# 1-Schematic_INFRARED_WAVER_V1.net
KiCad netlist of a schematic drawn in EasyEDA
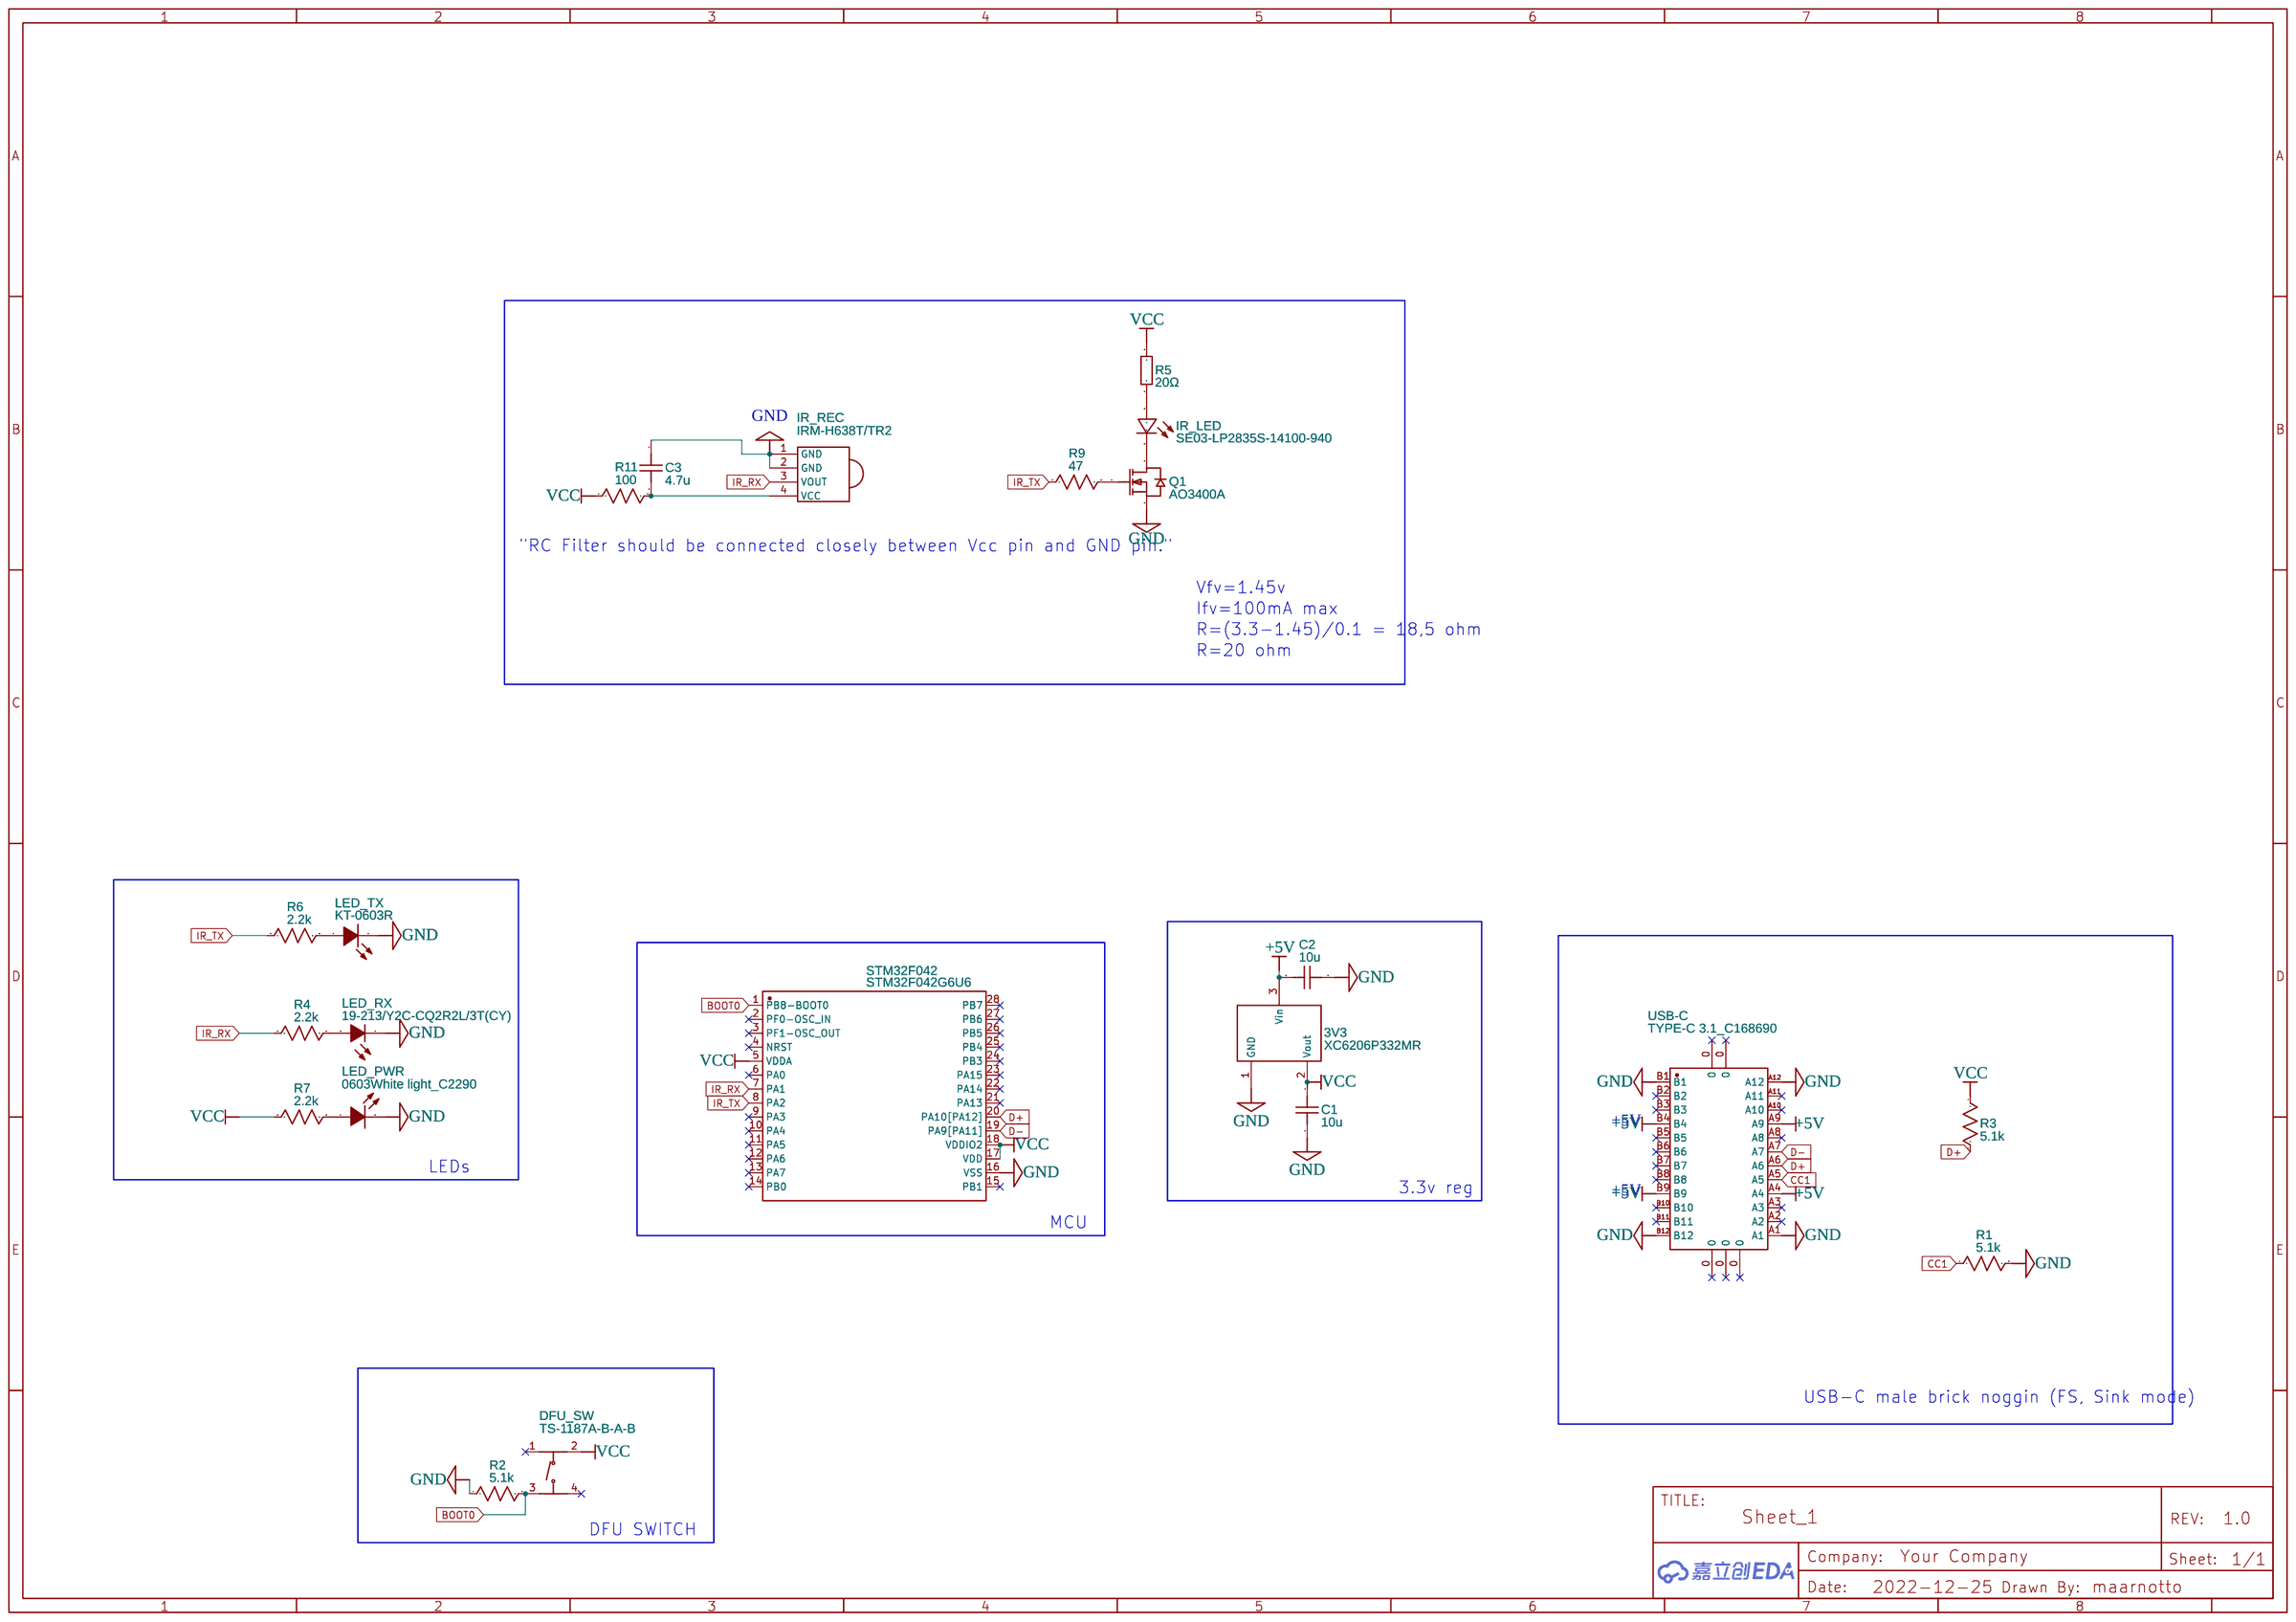
[diagram p0: schematic sheet]

(export (version "E")
  (design (tool "Eeschema 10.0.6"))
  (components
    (comp (ref "3V3")
      (value "XC6206P332MR")
      (fields (field (name "Manufacturer") "TOREX(特瑞仕)"))
      (libsource (lib "") (part "XC6206P332MR"))
    )
    (comp (ref "C1") (value "10u") (libsource (lib "") (part "C_0603_US_1")))
    (comp (ref "C2") (value "10u") (libsource (lib "") (part "C_0603_US")))
    (comp (ref "C3") (value "4.7u") (libsource (lib "") (part "C_0603_US_1")))
    (comp (ref "DFU_SW")
      (value "TS-1187A-B-A-B")
      (fields (field (name "Manufacturer") "XKB Connectivity(中国星坤)"))
      (libsource (lib "") (part "TS-1187A-B-A-B"))
    )
    (comp (ref "IR_LED")
      (value "SE03-LP2835S-14100-940")
      (fields (field (name "Manufacturer") "XSSY(旭晟)"))
      (libsource (lib "") (part "SE03-LP2835S-14100-940"))
    )
    (comp (ref "IR_REC")
      (value "IRM-H638T/TR2")
      (fields (field (name "Manufacturer") "EVERLIGHT(亿光)"))
      (libsource (lib "") (part "IRM-H638T/TR2"))
    )
    (comp (ref "LED_PWR")
      (value "0603White light_C2290")
      (fields (field (name "Manufacturer Part") "KT-0603白灯"))
      (libsource (lib "") (part "0603White light_C2290"))
    )
    (comp (ref "LED_RX")
      (value "19-213/Y2C-CQ2R2L/3T(CY)")
      (fields (field (name "Manufacturer") "EVERLIGHT(亿光)"))
      (libsource (lib "") (part "19-213/Y2C-CQ2R2L/3T(CY)"))
    )
    (comp (ref "LED_TX")
      (value "KT-0603R")
      (fields (field (name "Manufacturer") "KENTO"))
      (libsource (lib "") (part "KT-0603R"))
    )
    (comp (ref "Q1")
      (value "AO3400A")
      (fields (field (name "Manufacturer") "AOS"))
      (libsource (lib "") (part "AO3400A"))
    )
    (comp (ref "R1") (value "5.1k") (libsource (lib "") (part "R_0603_US_1")))
    (comp (ref "R2") (value "5.1k") (libsource (lib "") (part "R_0603_US_1")))
    (comp (ref "R3") (value "5.1k") (libsource (lib "") (part "R_0603_US")))
    (comp (ref "R4") (value "2.2k") (libsource (lib "") (part "R_0603_US_1")))
    (comp (ref "R5")
      (value "20Ω")
      (fields
        (field (name "Manufacturer Part") "1206W4F200JT5E")
        (field (name "Manufacturer") "UNI-ROYAL(厚声)")
      )
      (libsource (lib "") (part "1206W4F200JT5E"))
    )
    (comp (ref "R6") (value "2.2k") (libsource (lib "") (part "R_0603_US_1")))
    (comp (ref "R7") (value "2.2k") (libsource (lib "") (part "R_0603_US_1")))
    (comp (ref "R9") (value "47") (libsource (lib "") (part "R_0603_US_1")))
    (comp (ref "R11") (value "100") (libsource (lib "") (part "R_0603_US_1")))
    (comp (ref "STM32F042")
      (value "STM32F042G6U6")
      (fields (field (name "Manufacturer") "ST(意法半导体)"))
      (libsource (lib "") (part "STM32F042G6U6"))
    )
    (comp (ref "USB-C")
      (value "TYPE-C 3.1_C168690")
      (fields (field (name "Manufacturer Part") "918-118A2021Y40000") (field (name "Manufacturer") "精拓金"))
      (libsource (lib "") (part "TYPE-C 3.1_C168690"))
    )
  )
  (nets
    (net (code "1") (name "+5V") (class "Default")
      (node (ref "3V3") (pin "3") (pinfunction "Vin_3") (pintype "unspecified"))
      (node (ref "C2") (pin "2") (pinfunction "2_2") (pintype "unspecified"))
      (node (ref "USB-C") (pin "A4") (pinfunction "A4_A4") (pintype "unspecified"))
      (node (ref "USB-C") (pin "A9") (pinfunction "A9_A9") (pintype "unspecified"))
      (node (ref "USB-C") (pin "B4") (pinfunction "B4_B4") (pintype "unspecified"))
      (node (ref "USB-C") (pin "B9") (pinfunction "B9_B9") (pintype "unspecified"))
    )
    (net (code "2") (name "BOOT0") (class "Default")
      (node (ref "DFU_SW") (pin "3") (pinfunction "C_3") (pintype "unspecified"))
      (node (ref "R2") (pin "2") (pinfunction "2_2") (pintype "unspecified"))
      (node (ref "STM32F042") (pin "1") (pinfunction "PB8-BOOT0_1") (pintype "unspecified"))
    )
    (net (code "3") (name "CC1") (class "Default")
      (node (ref "R1") (pin "1") (pinfunction "1_1") (pintype "unspecified"))
      (node (ref "USB-C") (pin "A5") (pinfunction "A5_A5") (pintype "unspecified"))
    )
    (net (code "4") (name "D+") (class "Default")
      (node (ref "R3") (pin "2") (pinfunction "2_2") (pintype "unspecified"))
      (node (ref "STM32F042") (pin "20") (pinfunction "PA10[PA12]_20") (pintype "unspecified"))
      (node (ref "USB-C") (pin "A6") (pinfunction "A6_A6") (pintype "unspecified"))
    )
    (net (code "5") (name "D-") (class "Default")
      (node (ref "STM32F042") (pin "19") (pinfunction "PA9[PA11]_19") (pintype "unspecified"))
      (node (ref "USB-C") (pin "A7") (pinfunction "A7_A7") (pintype "unspecified"))
    )
    (net (code "6") (name "GND") (class "Default")
      (node (ref "3V3") (pin "1") (pinfunction "GND_1") (pintype "unspecified"))
      (node (ref "C1") (pin "2") (pinfunction "2_2") (pintype "unspecified"))
      (node (ref "C2") (pin "1") (pinfunction "1_1") (pintype "unspecified"))
      (node (ref "C3") (pin "1") (pinfunction "1_1") (pintype "unspecified"))
      (node (ref "IR_REC") (pin "1") (pinfunction "GND_1") (pintype "input"))
      (node (ref "IR_REC") (pin "2") (pinfunction "GND_2") (pintype "input"))
      (node (ref "LED_PWR") (pin "2") (pinfunction "K_2") (pintype "unspecified"))
      (node (ref "LED_RX") (pin "1") (pinfunction "C_1") (pintype "input"))
      (node (ref "LED_TX") (pin "1") (pinfunction "K_1") (pintype "unspecified"))
      (node (ref "Q1") (pin "2") (pinfunction "S_2") (pintype "unspecified"))
      (node (ref "R1") (pin "2") (pinfunction "2_2") (pintype "unspecified"))
      (node (ref "R2") (pin "1") (pinfunction "1_1") (pintype "unspecified"))
      (node (ref "STM32F042") (pin "16") (pinfunction "VSS_16") (pintype "unspecified"))
      (node (ref "USB-C") (pin "A1") (pinfunction "A1_A1") (pintype "unspecified"))
      (node (ref "USB-C") (pin "A12") (pinfunction "A12_A12") (pintype "unspecified"))
      (node (ref "USB-C") (pin "B1") (pinfunction "B1_B1") (pintype "unspecified"))
      (node (ref "USB-C") (pin "B12") (pinfunction "B12_B12") (pintype "unspecified"))
    )
    (net (code "7") (name "IR_RX") (class "Default")
      (node (ref "IR_REC") (pin "3") (pinfunction "VOUT_3") (pintype "input"))
      (node (ref "R4") (pin "1") (pinfunction "1_1") (pintype "unspecified"))
      (node (ref "STM32F042") (pin "7") (pinfunction "PA1_7") (pintype "unspecified"))
    )
    (net (code "8") (name "IR_TX") (class "Default")
      (node (ref "R6") (pin "1") (pinfunction "1_1") (pintype "unspecified"))
      (node (ref "R9") (pin "1") (pinfunction "1_1") (pintype "unspecified"))
      (node (ref "STM32F042") (pin "8") (pinfunction "PA2_8") (pintype "unspecified"))
    )
    (net (code "9") (name "Net-(IR_LED-A)") (class "Default")
      (node (ref "IR_LED") (pin "1") (pinfunction "A_1") (pintype "unspecified"))
      (node (ref "R5") (pin "2") (pinfunction "2_2") (pintype "input"))
    )
    (net (code "10") (name "Net-(IR_LED-C)") (class "Default")
      (node (ref "IR_LED") (pin "2") (pinfunction "C_2") (pintype "unspecified"))
      (node (ref "Q1") (pin "3") (pinfunction "D_3") (pintype "unspecified"))
    )
    (net (code "11") (name "Net-(IR_REC-VCC)") (class "Default")
      (node (ref "C3") (pin "2") (pinfunction "2_2") (pintype "unspecified"))
      (node (ref "IR_REC") (pin "4") (pinfunction "VCC_4") (pintype "input"))
      (node (ref "R11") (pin "2") (pinfunction "2_2") (pintype "unspecified"))
    )
    (net (code "12") (name "Net-(LED_PWR-A)") (class "Default")
      (node (ref "LED_PWR") (pin "1") (pinfunction "A_1") (pintype "unspecified"))
      (node (ref "R7") (pin "2") (pinfunction "2_2") (pintype "unspecified"))
    )
    (net (code "13") (name "Net-(LED_RX-A)") (class "Default")
      (node (ref "LED_RX") (pin "2") (pinfunction "A_2") (pintype "input"))
      (node (ref "R4") (pin "2") (pinfunction "2_2") (pintype "unspecified"))
    )
    (net (code "14") (name "Net-(LED_TX-A)") (class "Default")
      (node (ref "LED_TX") (pin "2") (pinfunction "A_2") (pintype "unspecified"))
      (node (ref "R6") (pin "2") (pinfunction "2_2") (pintype "unspecified"))
    )
    (net (code "15") (name "Net-(Q1-G)") (class "Default")
      (node (ref "Q1") (pin "1") (pinfunction "G_1") (pintype "unspecified"))
      (node (ref "R9") (pin "2") (pinfunction "2_2") (pintype "unspecified"))
    )
    (net (code "16") (name "VCC") (class "Default")
      (node (ref "3V3") (pin "2") (pinfunction "Vout_2") (pintype "unspecified"))
      (node (ref "C1") (pin "1") (pinfunction "1_1") (pintype "unspecified"))
      (node (ref "DFU_SW") (pin "2") (pinfunction "B_2") (pintype "unspecified"))
      (node (ref "R11") (pin "1") (pinfunction "1_1") (pintype "unspecified"))
      (node (ref "R3") (pin "1") (pinfunction "1_1") (pintype "unspecified"))
      (node (ref "R5") (pin "1") (pinfunction "1_1") (pintype "input"))
      (node (ref "R7") (pin "1") (pinfunction "1_1") (pintype "unspecified"))
      (node (ref "STM32F042") (pin "17") (pinfunction "VDD_17") (pintype "unspecified"))
      (node (ref "STM32F042") (pin "18") (pinfunction "VDDIO2_18") (pintype "unspecified"))
      (node (ref "STM32F042") (pin "5") (pinfunction "VDDA_5") (pintype "unspecified"))
    )
    (net (code "17") (name "unconnected-(DFU_SW-A-Pad1)") (class "Default")
      (node (ref "DFU_SW") (pin "1") (pinfunction "A_1") (pintype "unspecified+no_connect"))
    )
    (net (code "18") (name "unconnected-(DFU_SW-D-Pad4)") (class "Default")
      (node (ref "DFU_SW") (pin "4") (pinfunction "D_4") (pintype "unspecified+no_connect"))
    )
    (net (code "19") (name "unconnected-(STM32F042-NRST-Pad4)") (class "Default")
      (node (ref "STM32F042") (pin "4") (pinfunction "NRST_4") (pintype "unspecified+no_connect"))
    )
    (net (code "20") (name "unconnected-(STM32F042-PA0-Pad6)") (class "Default")
      (node (ref "STM32F042") (pin "6") (pinfunction "PA0_6") (pintype "unspecified+no_connect"))
    )
    (net (code "21") (name "unconnected-(STM32F042-PA3-Pad9)") (class "Default")
      (node (ref "STM32F042") (pin "9") (pinfunction "PA3_9") (pintype "unspecified+no_connect"))
    )
    (net (code "22") (name "unconnected-(STM32F042-PA4-Pad10)") (class "Default")
      (node (ref "STM32F042") (pin "10") (pinfunction "PA4_10") (pintype "unspecified+no_connect"))
    )
    (net (code "23") (name "unconnected-(STM32F042-PA5-Pad11)") (class "Default")
      (node (ref "STM32F042") (pin "11") (pinfunction "PA5_11") (pintype "unspecified+no_connect"))
    )
    (net (code "24") (name "unconnected-(STM32F042-PA6-Pad12)") (class "Default")
      (node (ref "STM32F042") (pin "12") (pinfunction "PA6_12") (pintype "unspecified+no_connect"))
    )
    (net (code "25") (name "unconnected-(STM32F042-PA7-Pad13)") (class "Default")
      (node (ref "STM32F042") (pin "13") (pinfunction "PA7_13") (pintype "unspecified+no_connect"))
    )
    (net (code "26") (name "unconnected-(STM32F042-PA13-Pad21)") (class "Default")
      (node (ref "STM32F042") (pin "21") (pinfunction "PA13_21") (pintype "unspecified+no_connect"))
    )
    (net (code "27") (name "unconnected-(STM32F042-PA14-Pad22)") (class "Default")
      (node (ref "STM32F042") (pin "22") (pinfunction "PA14_22") (pintype "unspecified+no_connect"))
    )
    (net (code "28") (name "unconnected-(STM32F042-PA15-Pad23)") (class "Default")
      (node (ref "STM32F042") (pin "23") (pinfunction "PA15_23") (pintype "unspecified+no_connect"))
    )
    (net (code "29") (name "unconnected-(STM32F042-PB0-Pad14)") (class "Default")
      (node (ref "STM32F042") (pin "14") (pinfunction "PB0_14") (pintype "unspecified+no_connect"))
    )
    (net (code "30") (name "unconnected-(STM32F042-PB1-Pad15)") (class "Default")
      (node (ref "STM32F042") (pin "15") (pinfunction "PB1_15") (pintype "unspecified+no_connect"))
    )
    (net (code "31") (name "unconnected-(STM32F042-PB3-Pad24)") (class "Default")
      (node (ref "STM32F042") (pin "24") (pinfunction "PB3_24") (pintype "unspecified+no_connect"))
    )
    (net (code "32") (name "unconnected-(STM32F042-PB4-Pad25)") (class "Default")
      (node (ref "STM32F042") (pin "25") (pinfunction "PB4_25") (pintype "unspecified+no_connect"))
    )
    (net (code "33") (name "unconnected-(STM32F042-PB5-Pad26)") (class "Default")
      (node (ref "STM32F042") (pin "26") (pinfunction "PB5_26") (pintype "unspecified+no_connect"))
    )
    (net (code "34") (name "unconnected-(STM32F042-PB6-Pad27)") (class "Default")
      (node (ref "STM32F042") (pin "27") (pinfunction "PB6_27") (pintype "unspecified+no_connect"))
    )
    (net (code "35") (name "unconnected-(STM32F042-PB7-Pad28)") (class "Default")
      (node (ref "STM32F042") (pin "28") (pinfunction "PB7_28") (pintype "unspecified+no_connect"))
    )
    (net (code "36") (name "unconnected-(STM32F042-PF0-OSC_IN-Pad2)") (class "Default")
      (node (ref "STM32F042") (pin "2") (pinfunction "PF0-OSC_IN_2") (pintype "unspecified+no_connect"))
    )
    (net (code "37") (name "unconnected-(STM32F042-PF1-OSC_OUT-Pad3)") (class "Default")
      (node (ref "STM32F042") (pin "3") (pinfunction "PF1-OSC_OUT_3") (pintype "unspecified+no_connect"))
    )
    (net (code "38") (name "unconnected-(USB-C-Pad0)") (class "Default")
      (node (ref "USB-C") (pin "0") (pinfunction "0_0") (pintype "unspecified+no_connect"))
    )
    (net (code "39") (name "unconnected-(USB-C-Pad0)_1") (class "Default")
      (node (ref "USB-C") (pin "0") (pinfunction "0_0") (pintype "unspecified+no_connect"))
    )
    (net (code "40") (name "unconnected-(USB-C-Pad0)_2") (class "Default")
      (node (ref "USB-C") (pin "0") (pinfunction "0_0") (pintype "unspecified+no_connect"))
    )
    (net (code "41") (name "unconnected-(USB-C-Pad0)_3") (class "Default")
      (node (ref "USB-C") (pin "0") (pinfunction "0_0") (pintype "unspecified+no_connect"))
    )
    (net (code "42") (name "unconnected-(USB-C-Pad0)_4") (class "Default")
      (node (ref "USB-C") (pin "0") (pinfunction "0_0") (pintype "unspecified+no_connect"))
    )
    (net (code "43") (name "unconnected-(USB-C-PadA2)") (class "Default")
      (node (ref "USB-C") (pin "A2") (pinfunction "A2_A2") (pintype "unspecified+no_connect"))
    )
    (net (code "44") (name "unconnected-(USB-C-PadA3)") (class "Default")
      (node (ref "USB-C") (pin "A3") (pinfunction "A3_A3") (pintype "unspecified+no_connect"))
    )
    (net (code "45") (name "unconnected-(USB-C-PadA8)") (class "Default")
      (node (ref "USB-C") (pin "A8") (pinfunction "A8_A8") (pintype "unspecified+no_connect"))
    )
    (net (code "46") (name "unconnected-(USB-C-PadA10)") (class "Default")
      (node (ref "USB-C") (pin "A10") (pinfunction "A10_A10") (pintype "unspecified+no_connect"))
    )
    (net (code "47") (name "unconnected-(USB-C-PadA11)") (class "Default")
      (node (ref "USB-C") (pin "A11") (pinfunction "A11_A11") (pintype "unspecified+no_connect"))
    )
    (net (code "48") (name "unconnected-(USB-C-PadB2)") (class "Default")
      (node (ref "USB-C") (pin "B2") (pinfunction "B2_B2") (pintype "unspecified+no_connect"))
    )
    (net (code "49") (name "unconnected-(USB-C-PadB3)") (class "Default")
      (node (ref "USB-C") (pin "B3") (pinfunction "B3_B3") (pintype "unspecified+no_connect"))
    )
    (net (code "50") (name "unconnected-(USB-C-PadB5)") (class "Default")
      (node (ref "USB-C") (pin "B5") (pinfunction "B5_B5") (pintype "unspecified+no_connect"))
    )
    (net (code "51") (name "unconnected-(USB-C-PadB6)") (class "Default")
      (node (ref "USB-C") (pin "B6") (pinfunction "B6_B6") (pintype "unspecified+no_connect"))
    )
    (net (code "52") (name "unconnected-(USB-C-PadB7)") (class "Default")
      (node (ref "USB-C") (pin "B7") (pinfunction "B7_B7") (pintype "unspecified+no_connect"))
    )
    (net (code "53") (name "unconnected-(USB-C-PadB8)") (class "Default")
      (node (ref "USB-C") (pin "B8") (pinfunction "B8_B8") (pintype "unspecified+no_connect"))
    )
    (net (code "54") (name "unconnected-(USB-C-PadB10)") (class "Default")
      (node (ref "USB-C") (pin "B10") (pinfunction "B10_B10") (pintype "unspecified+no_connect"))
    )
    (net (code "55") (name "unconnected-(USB-C-PadB11)") (class "Default")
      (node (ref "USB-C") (pin "B11") (pinfunction "B11_B11") (pintype "unspecified+no_connect"))
    )
  )
)
